# M4F_MCU.net
KiCad netlist of a schematic drawn in Altium Designer
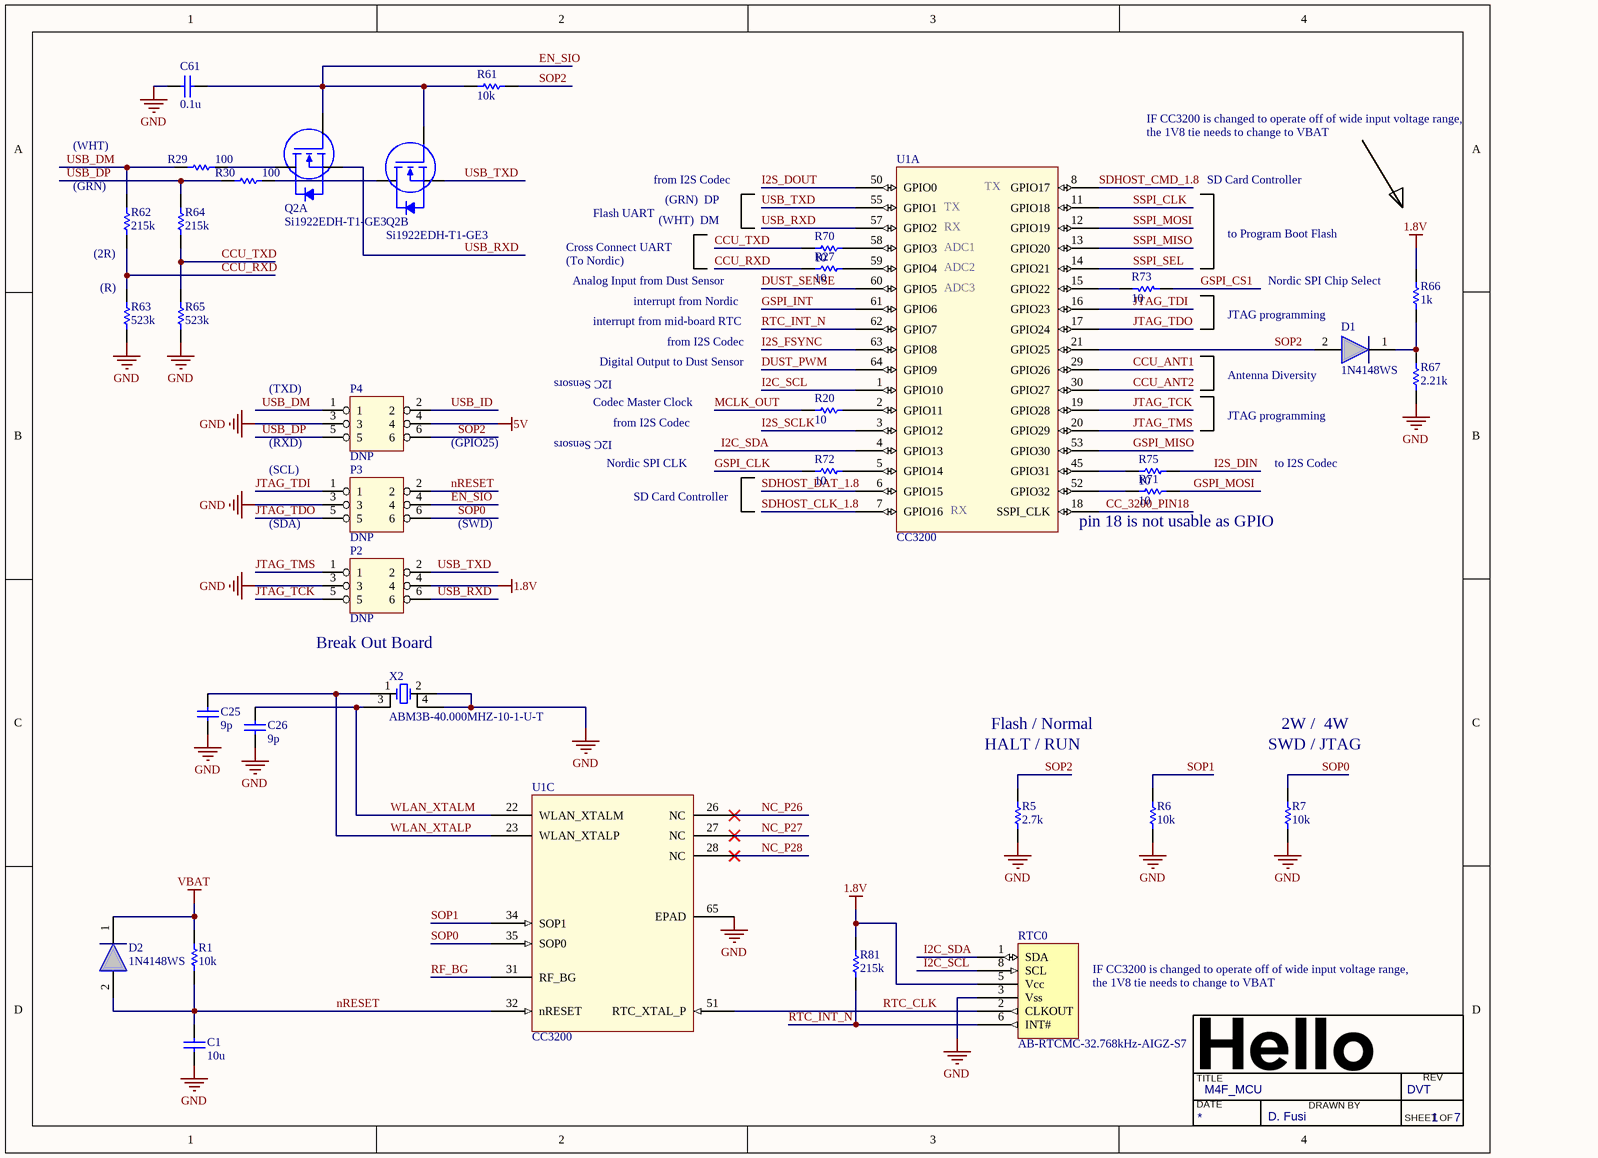
[diagram p0: M4F_MCU.SchDoc]

(export (version "E")
  (design (tool "Eeschema 10.0.6"))
  (components
    (comp (ref "C1")
      (value "10u")
      (footprint "CAP0603_SENSE_DVT")
      (description "Chip capacitor")
      (fields (field (name "TOLERANCE") "10%") (field (name "VOLTAGE") "6.3V"))
      (libsource (lib "Morpheus_pill") (part "C_10u_10_6.3_X5R_0603"))
    )
    (comp (ref "C25")
      (value "9p")
      (footprint "CAP0402_SENSE_DVT")
      (description "Chip capacitor")
      (fields (field (name "TOLERANCE") "0.1") (field (name "VOLTAGE") "50V"))
      (libsource (lib "Morpheus_pill") (part "C_9p_0.1_50_C0G_0402"))
    )
    (comp (ref "C26")
      (value "9p")
      (footprint "CAP0402_SENSE_DVT")
      (description "Chip capacitor")
      (fields (field (name "TOLERANCE") "0.1") (field (name "VOLTAGE") "50V"))
      (libsource (lib "Morpheus_pill") (part "C_9p_0.1_50_C0G_0402"))
    )
    (comp (ref "C61")
      (value "0.1u")
      (footprint "CAP0603_SENSE_DVT")
      (description "Chip capacitor")
      (fields (field (name "TOLERANCE") "20%") (field (name "VOLTAGE") "16V"))
      (libsource (lib "Morpheus_pill") (part "C_0.1u_20_16_X7R_0603"))
    )
    (comp (ref "D1")
      (value "1N4148WS")
      (footprint "SOD-323")
      (description "Standard diode, 75V 150mA")
      (libsource (lib "Morpheus_pill") (part "1N4148WS"))
    )
    (comp (ref "D2")
      (value "1N4148WS")
      (footprint "SOD-323")
      (description "Standard diode, 75V 150mA")
      (libsource (lib "Morpheus_pill") (part "1N4148WS"))
    )
    (comp (ref "P2")
      (value "DNP")
      (footprint "HDR2.00-2X3-SMD")
      (description "BOB headers")
      (libsource (lib "Morpheus_pill") (part "HDR2.00-2X3-SMD"))
    )
    (comp (ref "P3")
      (value "DNP")
      (footprint "HDR2.00-2X3-SMD")
      (description "BOB headers")
      (libsource (lib "Morpheus_pill") (part "HDR2.00-2X3-SMD"))
    )
    (comp (ref "P4")
      (value "DNP")
      (footprint "HDR2.00-2X3-SMD")
      (description "BOB headers")
      (libsource (lib "Morpheus_pill") (part "HDR2.00-2X3-SMD"))
    )
    (comp (ref "Q2")
      (value "Si1922EDH-T1-GE3")
      (footprint "SC-70-6")
      (description "Vishay Dual N-Channel MOSFET Si1922EDH-T1-GE3")
      (libsource (lib "Morpheus_pill") (part "Si1922EDH-T1-GE3"))
    )
    (comp (ref "R1")
      (value "10k")
      (footprint "RES0402_SENSE_DVT")
      (description "Chip Resistor")
      (fields (field (name "TOLERANCE") "5 %") (field (name "POWER") "0.1 W"))
      (libsource (lib "Morpheus_pill") (part "R_10k_5_0.1_0402"))
    )
    (comp (ref "R5")
      (value "2.7k")
      (footprint "RES0402_SENSE_DVT")
      (description "Chip Resistor")
      (fields (field (name "TOLERANCE") "5 %") (field (name "POWER") "0.1 W"))
      (libsource (lib "Morpheus_pill") (part "R_2.7k_5_0.1_0402"))
    )
    (comp (ref "R6")
      (value "10k")
      (footprint "RES0402_SENSE_DVT")
      (description "Chip Resistor")
      (fields (field (name "TOLERANCE") "5 %") (field (name "POWER") "0.1 W"))
      (libsource (lib "Morpheus_pill") (part "R_10k_5_0.1_0402"))
    )
    (comp (ref "R7")
      (value "10k")
      (footprint "RES0402_SENSE_DVT")
      (description "Chip Resistor")
      (fields (field (name "TOLERANCE") "5 %") (field (name "POWER") "0.1 W"))
      (libsource (lib "Morpheus_pill") (part "R_10k_5_0.1_0402"))
    )
    (comp (ref "R20")
      (value "10")
      (footprint "RES0402_SENSE_DVT")
      (description "Chip Resistor")
      (fields (field (name "TOLERANCE") "1 %") (field (name "POWER") "0.1 W"))
      (libsource (lib "Morpheus_pill") (part "R_10_1_0.1_0402"))
    )
    (comp (ref "R27")
      (value "10")
      (footprint "RES0402_SENSE_DVT")
      (description "Chip Resistor")
      (fields (field (name "TOLERANCE") "1 %") (field (name "POWER") "0.1 W"))
      (libsource (lib "Morpheus_pill") (part "R_10_1_0.1_0402"))
    )
    (comp (ref "R29")
      (value "100")
      (footprint "RES0402_SENSE_DVT")
      (description "Chip Resistor")
      (fields (field (name "TOLERANCE") "1 %") (field (name "POWER") "0.1 W"))
      (libsource (lib "Morpheus_pill") (part "R_100_1_0.1_0402"))
    )
    (comp (ref "R30")
      (value "100")
      (footprint "RES0402_SENSE_DVT")
      (description "Chip Resistor")
      (fields (field (name "TOLERANCE") "1 %") (field (name "POWER") "0.1 W"))
      (libsource (lib "Morpheus_pill") (part "R_100_1_0.1_0402"))
    )
    (comp (ref "R61")
      (value "10k")
      (footprint "RES0402_SENSE_DVT")
      (description "Chip Resistor")
      (fields (field (name "TOLERANCE") "5 %") (field (name "POWER") "0.1 W"))
      (libsource (lib "Morpheus_pill") (part "R_10k_5_0.1_0402"))
    )
    (comp (ref "R62")
      (value "215k")
      (footprint "RES0402_SENSE_DVT")
      (description "Chip Resistor")
      (fields (field (name "TOLERANCE") "1 %") (field (name "POWER") "0.1 W"))
      (libsource (lib "Morpheus_pill") (part "R_215K_1_0.1_0402"))
    )
    (comp (ref "R63")
      (value "523k")
      (footprint "RES0402_SENSE_DVT")
      (description "Chip Resistor")
      (fields (field (name "TOLERANCE") "1 %") (field (name "POWER") "0.1 W"))
      (libsource (lib "Morpheus_pill") (part "R_523k_1_0.1_0402"))
    )
    (comp (ref "R64")
      (value "215k")
      (footprint "RES0402_SENSE_DVT")
      (description "Chip Resistor")
      (fields (field (name "TOLERANCE") "1 %") (field (name "POWER") "0.1 W"))
      (libsource (lib "Morpheus_pill") (part "R_215K_1_0.1_0402"))
    )
    (comp (ref "R65")
      (value "523k")
      (footprint "RES0402_SENSE_DVT")
      (description "Chip Resistor")
      (fields (field (name "TOLERANCE") "1 %") (field (name "POWER") "0.1 W"))
      (libsource (lib "Morpheus_pill") (part "R_523k_1_0.1_0402"))
    )
    (comp (ref "R66")
      (value "1k")
      (footprint "RES0402_SENSE_DVT")
      (description "Chip Resistor")
      (fields (field (name "TOLERANCE") "1 %") (field (name "POWER") "0.1 W"))
      (libsource (lib "Morpheus_pill") (part "R_1k_1_0.1_0402"))
    )
    (comp (ref "R67")
      (value "2.21k")
      (footprint "RES0402")
      (description "Chip Resistor")
      (fields (field (name "TOLERANCE") "1 %") (field (name "POWER") "0.1 W"))
      (libsource (lib "Morpheus_pill") (part "R_2.21k_1_0.1_0402"))
    )
    (comp (ref "R70")
      (value "10")
      (footprint "RES0402_SENSE_DVT")
      (description "Chip Resistor")
      (fields (field (name "TOLERANCE") "1 %") (field (name "POWER") "0.1 W"))
      (libsource (lib "Morpheus_pill") (part "R_10_1_0.1_0402"))
    )
    (comp (ref "R71")
      (value "10")
      (footprint "RES0402_SENSE_DVT")
      (description "Chip Resistor")
      (fields (field (name "TOLERANCE") "1 %") (field (name "POWER") "0.1 W"))
      (libsource (lib "Morpheus_pill") (part "R_10_1_0.1_0402"))
    )
    (comp (ref "R72")
      (value "10")
      (footprint "RES0402_SENSE_DVT")
      (description "Chip Resistor")
      (fields (field (name "TOLERANCE") "1 %") (field (name "POWER") "0.1 W"))
      (libsource (lib "Morpheus_pill") (part "R_10_1_0.1_0402"))
    )
    (comp (ref "R73")
      (value "10")
      (footprint "RES0402_SENSE_DVT")
      (description "Chip Resistor")
      (fields (field (name "TOLERANCE") "1 %") (field (name "POWER") "0.1 W"))
      (libsource (lib "Morpheus_pill") (part "R_10_1_0.1_0402"))
    )
    (comp (ref "R75")
      (value "10")
      (footprint "RES0402_SENSE_DVT")
      (description "Chip Resistor")
      (fields (field (name "TOLERANCE") "1 %") (field (name "POWER") "0.1 W"))
      (libsource (lib "Morpheus_pill") (part "R_10_1_0.1_0402"))
    )
    (comp (ref "R81")
      (value "215k")
      (footprint "RES0402_SENSE_DVT")
      (description "Chip Resistor")
      (fields (field (name "TOLERANCE") "1 %") (field (name "POWER") "0.1 W"))
      (libsource (lib "Morpheus_pill") (part "R_215K_1_0.1_0402"))
    )
    (comp (ref "RTC0")
      (value "AB-RTCMC-32.768kHz-AIGZ-S7")
      (footprint "8-CLCC")
      (description "Abracon I2C RTC w/ integrated XO")
      (libsource (lib "Morpheus_pill") (part "AB-RTCMC-32.768kHz-AIGZ-S7"))
    )
    (comp (ref "U1")
      (value "CC3200")
      (footprint "QFN50P900X900X100_HS-65N")
      (description "TI Wi-FI module")
      (libsource (lib "Morpheus_pill") (part "CC3200"))
    )
    (comp (ref "X2")
      (value "ABM3B-40.000MHZ-10-1-U-T")
      (footprint "ABM3B_CRYSTAL")
      (description "Abracon 40 MHz crystal")
      (libsource (lib "Morpheus_pill") (part "Crystal_40M_50_50_18_50"))
    )
  )
  (nets
    (net (code "1") (name "/CCU_ANT1") (class "Default")
      (node (ref "U1") (pin "29") (pinfunction "GPIO26_29") (pintype "bidirectional"))
    )
    (net (code "2") (name "/CCU_ANT2") (class "Default")
      (node (ref "U1") (pin "30") (pinfunction "GPIO27_30") (pintype "bidirectional"))
    )
    (net (code "3") (name "/CCU_RXD") (class "Default")
      (node (ref "R27") (pin "2") (pinfunction "2_2") (pintype "passive"))
      (node (ref "R62") (pin "1") (pinfunction "1_1") (pintype "passive"))
      (node (ref "R63") (pin "2") (pinfunction "2_2") (pintype "passive"))
    )
    (net (code "4") (name "/CCU_TXD") (class "Default")
      (node (ref "R64") (pin "1") (pinfunction "1_1") (pintype "passive"))
      (node (ref "R65") (pin "2") (pinfunction "2_2") (pintype "passive"))
      (node (ref "R70") (pin "2") (pinfunction "2_2") (pintype "passive"))
    )
    (net (code "5") (name "/CC_3200_PIN18") (class "Default")
      (node (ref "U1") (pin "18") (pinfunction "SSPI_CLK_18") (pintype "bidirectional"))
    )
    (net (code "6") (name "/DUST_PWM") (class "Default")
      (node (ref "U1") (pin "64") (pinfunction "GPIO9_64") (pintype "bidirectional"))
    )
    (net (code "7") (name "/DUST_SENSE") (class "Default")
      (node (ref "U1") (pin "60") (pinfunction "GPIO5_60") (pintype "bidirectional"))
    )
    (net (code "8") (name "/EN_SIO") (class "Default")
      (node (ref "C61") (pin "1") (pinfunction "1_1") (pintype "passive"))
      (node (ref "P3") (pin "4") (pinfunction "4_4") (pintype "passive"))
      (node (ref "Q2") (pin "2") (pinfunction "G1_2") (pintype "passive"))
      (node (ref "Q2") (pin "5") (pinfunction "G2_5") (pintype "passive"))
      (node (ref "R61") (pin "2") (pinfunction "2_2") (pintype "passive"))
    )
    (net (code "9") (name "/GSPI_CLK") (class "Default")
      (node (ref "R72") (pin "2") (pinfunction "2_2") (pintype "passive"))
    )
    (net (code "10") (name "/GSPI_CS1") (class "Default")
      (node (ref "R73") (pin "2") (pinfunction "2_2") (pintype "passive"))
    )
    (net (code "11") (name "/GSPI_INT") (class "Default")
      (node (ref "U1") (pin "61") (pinfunction "GPIO6_61") (pintype "bidirectional"))
    )
    (net (code "12") (name "/GSPI_MISO") (class "Default")
      (node (ref "U1") (pin "53") (pinfunction "GPIO30_53") (pintype "bidirectional"))
    )
    (net (code "13") (name "/GSPI_MOSI") (class "Default")
      (node (ref "R71") (pin "1") (pinfunction "1_1") (pintype "passive"))
    )
    (net (code "14") (name "/I2C_SCL") (class "Default")
      (node (ref "RTC0") (pin "8") (pinfunction "SCL_8") (pintype "input"))
      (node (ref "U1") (pin "1") (pinfunction "GPIO10_1") (pintype "bidirectional"))
    )
    (net (code "15") (name "/I2C_SDA") (class "Default")
      (node (ref "RTC0") (pin "1") (pinfunction "SDA_1") (pintype "bidirectional"))
      (node (ref "U1") (pin "4") (pinfunction "GPIO13_4") (pintype "bidirectional"))
    )
    (net (code "16") (name "/I2S_DIN") (class "Default")
      (node (ref "R75") (pin "1") (pinfunction "1_1") (pintype "passive"))
    )
    (net (code "17") (name "/I2S_DOUT") (class "Default")
      (node (ref "U1") (pin "50") (pinfunction "GPIO0_50") (pintype "bidirectional"))
    )
    (net (code "18") (name "/I2S_FSYNC") (class "Default")
      (node (ref "U1") (pin "63") (pinfunction "GPIO8_63") (pintype "bidirectional"))
    )
    (net (code "19") (name "/I2S_SCLK") (class "Default")
      (node (ref "U1") (pin "3") (pinfunction "GPIO12_3") (pintype "bidirectional"))
    )
    (net (code "20") (name "/JTAG_TCK") (class "Default")
      (node (ref "P2") (pin "5") (pinfunction "5_5") (pintype "passive"))
      (node (ref "U1") (pin "19") (pinfunction "GPIO28_19") (pintype "bidirectional"))
    )
    (net (code "21") (name "/JTAG_TDI") (class "Default")
      (node (ref "P3") (pin "1") (pinfunction "1_1") (pintype "passive"))
      (node (ref "U1") (pin "16") (pinfunction "GPIO23_16") (pintype "bidirectional"))
    )
    (net (code "22") (name "/JTAG_TDO") (class "Default")
      (node (ref "P3") (pin "5") (pinfunction "5_5") (pintype "passive"))
      (node (ref "U1") (pin "17") (pinfunction "GPIO24_17") (pintype "bidirectional"))
    )
    (net (code "23") (name "/JTAG_TMS") (class "Default")
      (node (ref "P2") (pin "1") (pinfunction "1_1") (pintype "passive"))
      (node (ref "U1") (pin "20") (pinfunction "GPIO29_20") (pintype "bidirectional"))
    )
    (net (code "24") (name "/MCLK_OUT") (class "Default")
      (node (ref "R20") (pin "2") (pinfunction "2_2") (pintype "passive"))
    )
    (net (code "25") (name "/NC_P26") (class "Default")
      (node (ref "U1") (pin "26") (pinfunction "NC_26") (pintype "passive+no_connect"))
    )
    (net (code "26") (name "/NC_P27") (class "Default")
      (node (ref "U1") (pin "27") (pinfunction "NC_27") (pintype "passive+no_connect"))
    )
    (net (code "27") (name "/NC_P28") (class "Default")
      (node (ref "U1") (pin "28") (pinfunction "NC_28") (pintype "passive+no_connect"))
    )
    (net (code "28") (name "/RF_BG") (class "Default")
      (node (ref "U1") (pin "31") (pinfunction "RF_BG_31") (pintype "passive"))
    )
    (net (code "29") (name "/RTC_CLK") (class "Default")
      (node (ref "RTC0") (pin "2") (pinfunction "CLKOUT_2") (pintype "output"))
      (node (ref "U1") (pin "51") (pinfunction "RTC_XTAL_P_51") (pintype "input"))
    )
    (net (code "30") (name "/RTC_INT_N") (class "Default")
      (node (ref "R81") (pin "1") (pinfunction "1_1") (pintype "passive"))
      (node (ref "RTC0") (pin "6") (pinfunction "INT#_6") (pintype "output"))
      (node (ref "U1") (pin "62") (pinfunction "GPIO7_62") (pintype "bidirectional"))
    )
    (net (code "31") (name "/SDHOST_CLK_1.8") (class "Default")
      (node (ref "U1") (pin "7") (pinfunction "GPIO16_7") (pintype "bidirectional"))
    )
    (net (code "32") (name "/SDHOST_CMD_1.8") (class "Default")
      (node (ref "U1") (pin "8") (pinfunction "GPIO17_8") (pintype "bidirectional"))
    )
    (net (code "33") (name "/SDHOST_DAT_1.8") (class "Default")
      (node (ref "U1") (pin "6") (pinfunction "GPIO15_6") (pintype "bidirectional"))
    )
    (net (code "34") (name "/SOP0") (class "Default")
      (node (ref "P3") (pin "6") (pinfunction "6_6") (pintype "passive"))
      (node (ref "R7") (pin "2") (pinfunction "2_2") (pintype "passive"))
      (node (ref "U1") (pin "35") (pinfunction "SOP0_35") (pintype "input"))
    )
    (net (code "35") (name "/SOP1") (class "Default")
      (node (ref "R6") (pin "2") (pinfunction "2_2") (pintype "passive"))
      (node (ref "U1") (pin "34") (pinfunction "SOP1_34") (pintype "input"))
    )
    (net (code "36") (name "/SOP2") (class "Default")
      (node (ref "D1") (pin "2") (pinfunction "Anode_2") (pintype "passive"))
      (node (ref "P4") (pin "6") (pinfunction "6_6") (pintype "passive"))
      (node (ref "R5") (pin "2") (pinfunction "2_2") (pintype "passive"))
      (node (ref "R61") (pin "1") (pinfunction "1_1") (pintype "passive"))
      (node (ref "U1") (pin "21") (pinfunction "GPIO25_21") (pintype "bidirectional"))
    )
    (net (code "37") (name "/SSPI_CLK") (class "Default")
      (node (ref "U1") (pin "11") (pinfunction "GPIO18_11") (pintype "bidirectional"))
    )
    (net (code "38") (name "/SSPI_MISO") (class "Default")
      (node (ref "U1") (pin "13") (pinfunction "GPIO20_13") (pintype "bidirectional"))
    )
    (net (code "39") (name "/SSPI_MOSI") (class "Default")
      (node (ref "U1") (pin "12") (pinfunction "GPIO19_12") (pintype "bidirectional"))
    )
    (net (code "40") (name "/SSPI_SEL") (class "Default")
      (node (ref "U1") (pin "14") (pinfunction "GPIO21_14") (pintype "bidirectional"))
    )
    (net (code "41") (name "/USB_DM") (class "Default")
      (node (ref "P4") (pin "1") (pinfunction "1_1") (pintype "passive"))
      (node (ref "R29") (pin "1") (pinfunction "1_1") (pintype "passive"))
      (node (ref "R62") (pin "2") (pinfunction "2_2") (pintype "passive"))
    )
    (net (code "42") (name "/USB_DP") (class "Default")
      (node (ref "P4") (pin "5") (pinfunction "5_5") (pintype "passive"))
      (node (ref "R30") (pin "1") (pinfunction "1_1") (pintype "passive"))
      (node (ref "R64") (pin "2") (pinfunction "2_2") (pintype "passive"))
    )
    (net (code "43") (name "/USB_ID") (class "Default")
      (node (ref "P4") (pin "2") (pinfunction "2_2") (pintype "passive"))
    )
    (net (code "44") (name "/USB_RXD") (class "Default")
      (node (ref "P2") (pin "6") (pinfunction "6_6") (pintype "passive"))
      (node (ref "Q2") (pin "1") (pinfunction "S1_1") (pintype "passive"))
      (node (ref "U1") (pin "57") (pinfunction "GPIO2_57") (pintype "bidirectional"))
    )
    (net (code "45") (name "/USB_TXD") (class "Default")
      (node (ref "P2") (pin "2") (pinfunction "2_2") (pintype "passive"))
      (node (ref "Q2") (pin "4") (pinfunction "S2_4") (pintype "passive"))
      (node (ref "U1") (pin "55") (pinfunction "GPIO1_55") (pintype "bidirectional"))
    )
    (net (code "46") (name "/WLAN_XTALM") (class "Default")
      (node (ref "C26") (pin "2") (pinfunction "2_2") (pintype "passive"))
      (node (ref "U1") (pin "22") (pinfunction "WLAN_XTALM_22") (pintype "passive"))
      (node (ref "X2") (pin "3") (pinfunction "3_3") (pintype "passive"))
    )
    (net (code "47") (name "/WLAN_XTALP") (class "Default")
      (node (ref "C25") (pin "2") (pinfunction "2_2") (pintype "passive"))
      (node (ref "U1") (pin "23") (pinfunction "WLAN_XTALP_23") (pintype "passive"))
      (node (ref "X2") (pin "1") (pinfunction "1_1") (pintype "passive"))
    )
    (net (code "48") (name "/nRESET") (class "Default")
      (node (ref "C1") (pin "2") (pinfunction "2_2") (pintype "passive"))
      (node (ref "D2") (pin "2") (pinfunction "Anode_2") (pintype "passive"))
      (node (ref "P3") (pin "2") (pinfunction "2_2") (pintype "passive"))
      (node (ref "R1") (pin "1") (pinfunction "1_1") (pintype "passive"))
      (node (ref "U1") (pin "32") (pinfunction "nRESET_32") (pintype "input"))
    )
    (net (code "49") (name "1.8V") (class "Default")
      (node (ref "P2") (pin "4") (pinfunction "4_4") (pintype "passive"))
      (node (ref "R66") (pin "2") (pinfunction "2_2") (pintype "passive"))
      (node (ref "R81") (pin "2") (pinfunction "2_2") (pintype "passive"))
      (node (ref "RTC0") (pin "5") (pinfunction "Vcc_5") (pintype "power_in"))
    )
    (net (code "50") (name "5V") (class "Default")
      (node (ref "P4") (pin "4") (pinfunction "4_4") (pintype "passive"))
    )
    (net (code "51") (name "GND") (class "Default")
      (node (ref "C1") (pin "1") (pinfunction "1_1") (pintype "passive"))
      (node (ref "C25") (pin "1") (pinfunction "1_1") (pintype "passive"))
      (node (ref "C26") (pin "1") (pinfunction "1_1") (pintype "passive"))
      (node (ref "C61") (pin "2") (pinfunction "2_2") (pintype "passive"))
      (node (ref "P2") (pin "3") (pinfunction "3_3") (pintype "passive"))
      (node (ref "P3") (pin "3") (pinfunction "3_3") (pintype "passive"))
      (node (ref "P4") (pin "3") (pinfunction "3_3") (pintype "passive"))
      (node (ref "R5") (pin "1") (pinfunction "1_1") (pintype "passive"))
      (node (ref "R6") (pin "1") (pinfunction "1_1") (pintype "passive"))
      (node (ref "R63") (pin "1") (pinfunction "1_1") (pintype "passive"))
      (node (ref "R65") (pin "1") (pinfunction "1_1") (pintype "passive"))
      (node (ref "R67") (pin "1") (pinfunction "1_1") (pintype "passive"))
      (node (ref "R7") (pin "1") (pinfunction "1_1") (pintype "passive"))
      (node (ref "RTC0") (pin "3") (pinfunction "Vss_3") (pintype "power_in"))
      (node (ref "U1") (pin "65") (pinfunction "EPAD_65") (pintype "passive"))
      (node (ref "X2") (pin "2") (pinfunction "2_2") (pintype "passive"))
      (node (ref "X2") (pin "4") (pinfunction "4_4") (pintype "passive"))
    )
    (net (code "52") (name "Net-(D1-Cathode)") (class "Default")
      (node (ref "D1") (pin "1") (pinfunction "Cathode_1") (pintype "passive"))
      (node (ref "R66") (pin "1") (pinfunction "1_1") (pintype "passive"))
      (node (ref "R67") (pin "2") (pinfunction "2_2") (pintype "passive"))
    )
    (net (code "53") (name "Net-(Q2A-D1)") (class "Default")
      (node (ref "Q2") (pin "6") (pinfunction "D1_6") (pintype "passive"))
      (node (ref "R29") (pin "2") (pinfunction "2_2") (pintype "passive"))
    )
    (net (code "54") (name "Net-(Q2B-D2)") (class "Default")
      (node (ref "Q2") (pin "3") (pinfunction "D2_3") (pintype "passive"))
      (node (ref "R30") (pin "2") (pinfunction "2_2") (pintype "passive"))
    )
    (net (code "55") (name "Net-(U1A-GPIO3)") (class "Default")
      (node (ref "R70") (pin "1") (pinfunction "1_1") (pintype "passive"))
      (node (ref "U1") (pin "58") (pinfunction "GPIO3_58") (pintype "bidirectional"))
    )
    (net (code "56") (name "Net-(U1A-GPIO4)") (class "Default")
      (node (ref "R27") (pin "1") (pinfunction "1_1") (pintype "passive"))
      (node (ref "U1") (pin "59") (pinfunction "GPIO4_59") (pintype "bidirectional"))
    )
    (net (code "57") (name "Net-(U1A-GPIO11)") (class "Default")
      (node (ref "R20") (pin "1") (pinfunction "1_1") (pintype "passive"))
      (node (ref "U1") (pin "2") (pinfunction "GPIO11_2") (pintype "bidirectional"))
    )
    (net (code "58") (name "Net-(U1A-GPIO14)") (class "Default")
      (node (ref "R72") (pin "1") (pinfunction "1_1") (pintype "passive"))
      (node (ref "U1") (pin "5") (pinfunction "GPIO14_5") (pintype "bidirectional"))
    )
    (net (code "59") (name "Net-(U1A-GPIO22)") (class "Default")
      (node (ref "R73") (pin "1") (pinfunction "1_1") (pintype "passive"))
      (node (ref "U1") (pin "15") (pinfunction "GPIO22_15") (pintype "bidirectional"))
    )
    (net (code "60") (name "Net-(U1A-GPIO31)") (class "Default")
      (node (ref "R75") (pin "2") (pinfunction "2_2") (pintype "passive"))
      (node (ref "U1") (pin "45") (pinfunction "GPIO31_45") (pintype "bidirectional"))
    )
    (net (code "61") (name "Net-(U1A-GPIO32)") (class "Default")
      (node (ref "R71") (pin "2") (pinfunction "2_2") (pintype "passive"))
      (node (ref "U1") (pin "52") (pinfunction "GPIO32_52") (pintype "bidirectional"))
    )
    (net (code "62") (name "VBAT") (class "Default")
      (node (ref "D2") (pin "1") (pinfunction "Cathode_1") (pintype "passive"))
      (node (ref "R1") (pin "2") (pinfunction "2_2") (pintype "passive"))
    )
    (net (code "63") (name "unconnected-(RTC0-NC-Pad4)") (class "Default")
      (node (ref "RTC0") (pin "4") (pinfunction "NC_4") (pintype "passive"))
    )
    (net (code "64") (name "unconnected-(RTC0-NC-Pad7)") (class "Default")
      (node (ref "RTC0") (pin "7") (pinfunction "NC_7") (pintype "passive"))
    )
  )
)
